# CHIP_ziffy_v4.net
KiCad netlist of a schematic drawn in EAGLE
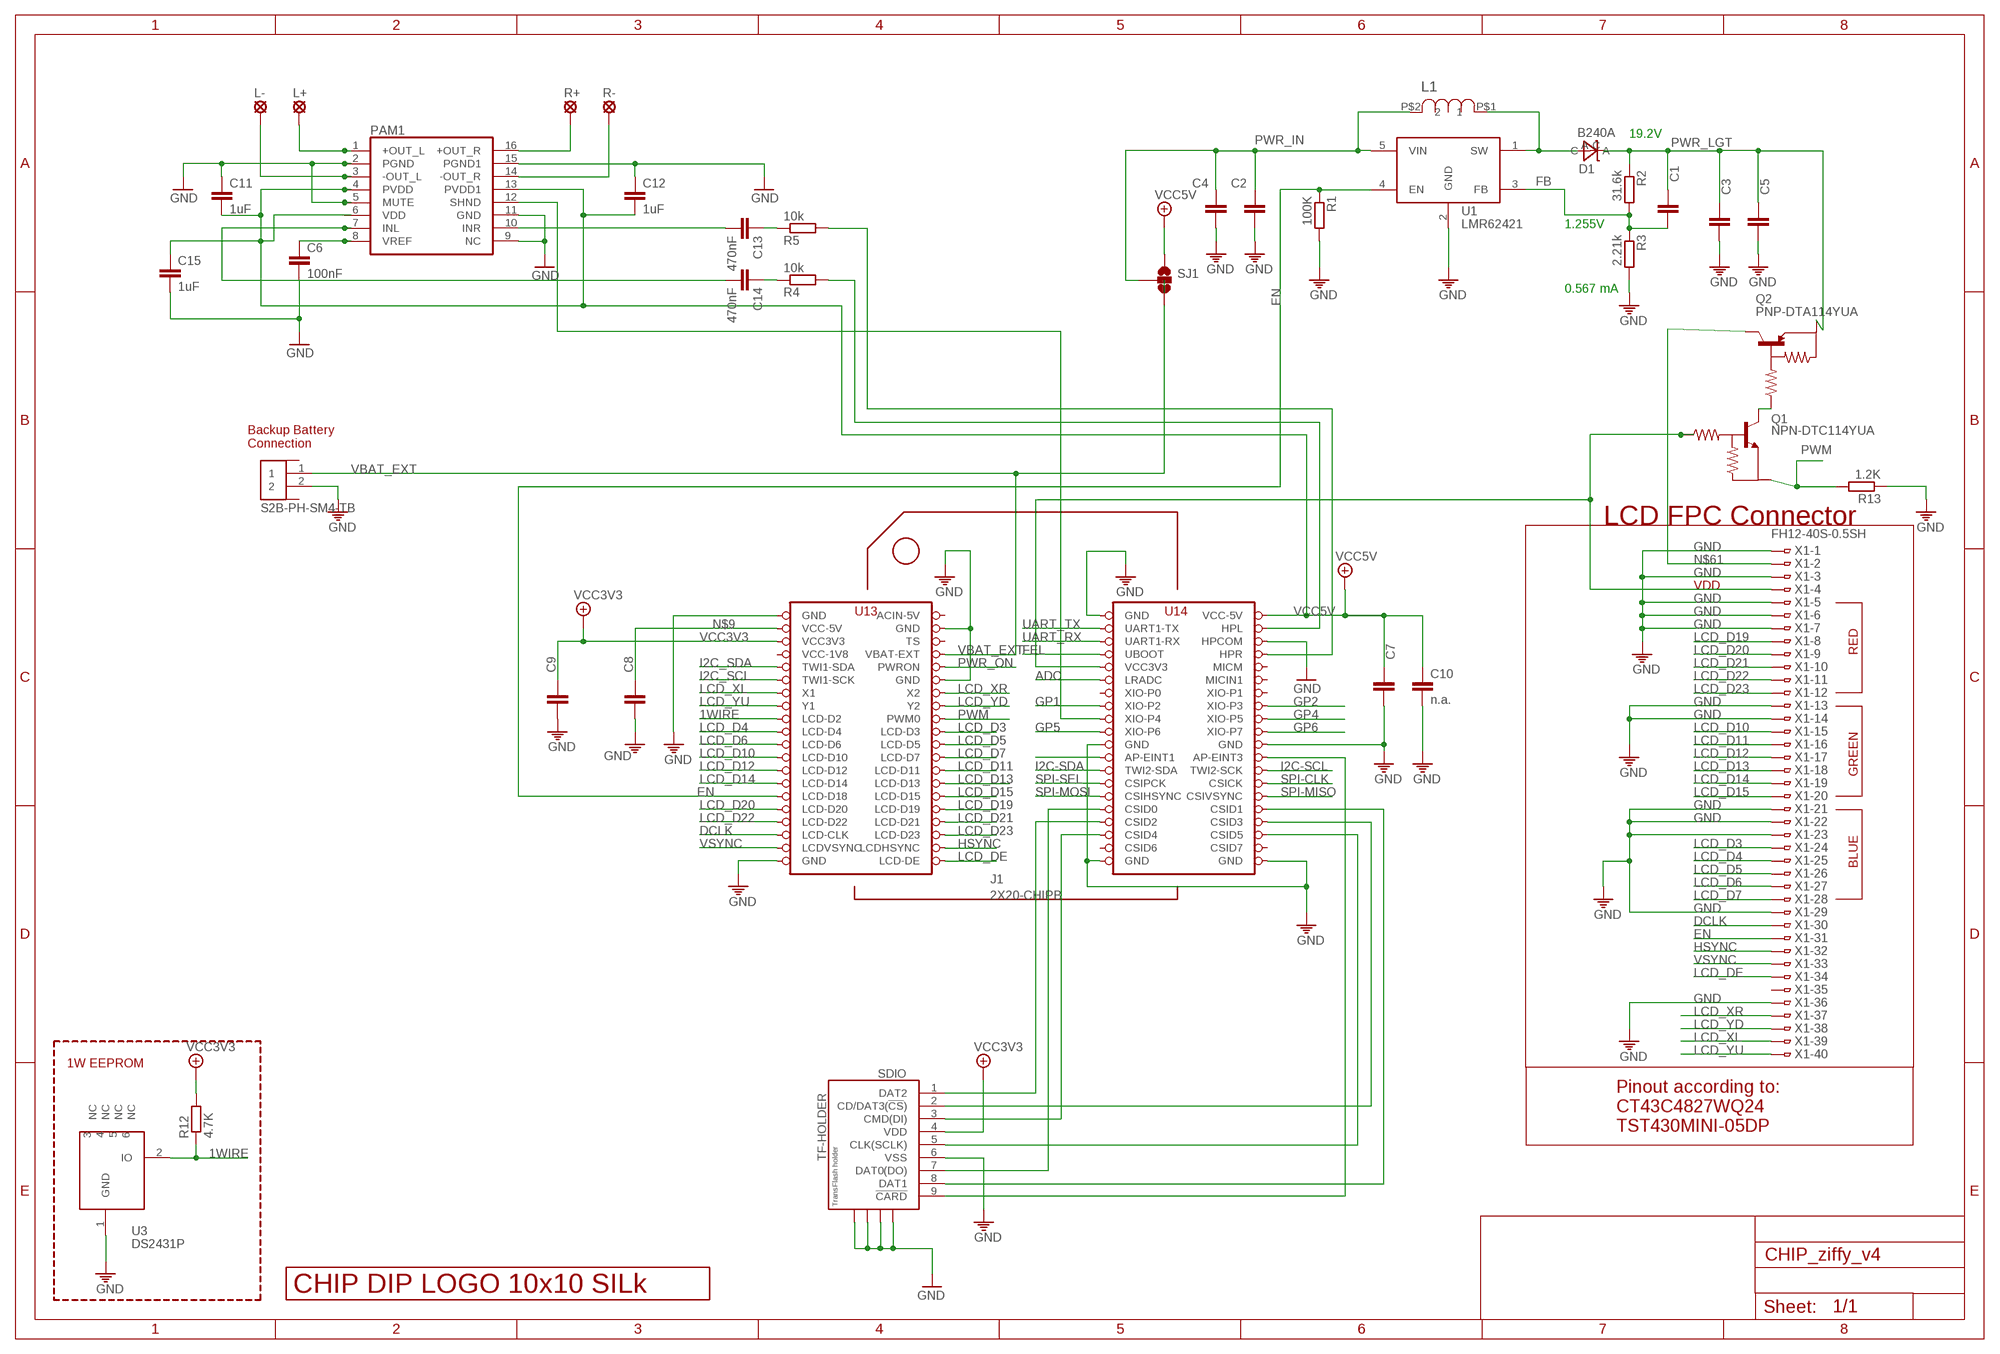
[diagram p0: schematic, sheet 1]

(export (version "E")
  (design (tool "Eeschema 10.0.6"))
  (components
    (comp (ref "C1")
      (value "220pF")
      (footprint "eagle-import:C0805")
      (libsource (lib "eagle-import") (part "C-EUC0805"))
    )
    (comp (ref "C2")
      (value "100nF")
      (footprint "eagle-import:C0805")
      (libsource (lib "eagle-import") (part "C-EUC0805"))
    )
    (comp (ref "C3")
      (value "100nF")
      (footprint "eagle-import:C0805")
      (libsource (lib "eagle-import") (part "C-EUC0805"))
    )
    (comp (ref "C4")
      (value "22uF")
      (footprint "eagle-import:C0805")
      (libsource (lib "eagle-import") (part "C-EUC0805"))
    )
    (comp (ref "C5")
      (value "22uF")
      (footprint "eagle-import:C0805")
      (libsource (lib "eagle-import") (part "C-EUC0805"))
    )
    (comp (ref "C6")
      (value "100nF")
      (footprint "eagle-import:C0805")
      (libsource (lib "eagle-import") (part "C-EUC0805"))
    )
    (comp (ref "C7")
      (value "n.a.")
      (footprint "eagle-import:C0805")
      (libsource (lib "eagle-import") (part "C-EUC0805"))
    )
    (comp (ref "C8")
      (value "100nF")
      (footprint "eagle-import:C0805")
      (libsource (lib "eagle-import") (part "C-EUC0805"))
    )
    (comp (ref "C9")
      (value "100nF")
      (footprint "eagle-import:C0805")
      (libsource (lib "eagle-import") (part "C-EUC0805"))
    )
    (comp (ref "C10")
      (value "n.a.")
      (footprint "eagle-import:C0805")
      (libsource (lib "eagle-import") (part "C-EUC0805"))
    )
    (comp (ref "C11")
      (value "1uF")
      (footprint "eagle-import:C0805")
      (libsource (lib "eagle-import") (part "C-EUC0805"))
    )
    (comp (ref "C12")
      (value "1uF")
      (footprint "eagle-import:C0805")
      (libsource (lib "eagle-import") (part "C-EUC0805"))
    )
    (comp (ref "C13")
      (value "470nF")
      (footprint "eagle-import:C0805")
      (libsource (lib "eagle-import") (part "C-EUC0805"))
    )
    (comp (ref "C14")
      (value "470nF")
      (footprint "eagle-import:C0805")
      (libsource (lib "eagle-import") (part "C-EUC0805"))
    )
    (comp (ref "C15")
      (value "1uF")
      (footprint "eagle-import:C0805")
      (libsource (lib "eagle-import") (part "C-EUC0805"))
    )
    (comp (ref "D1")
      (value "B240A")
      (footprint "eagle-import:DO-214AC")
      (fields (field (name "MFG") "DIGIKEY") (field (name "VENDOR_PART_NUMBER") "B240A-13-F"))
      (libsource (lib "eagle-import") (part "DIODE_SCHTKY_B240"))
    )
    (comp (ref "J1")
      (value "2X20-CHIPB")
      (footprint "eagle-import:2X20CHIP_SM")
      (libsource (lib "eagle-import") (part "2X20-CHIPB"))
    )
    (comp (ref "J3")
      (value "S2B-PH-SM4-TB")
      (footprint "eagle-import:S2B-PH-SM4-TB")
      (fields (field (name "MFG") "DIGIKEY") (field (name "VENDOR_PART_NUMBER") "S2B-PH-SM4-TB(LF)(SN)"))
      (libsource (lib "eagle-import") (part "S2B-PH-SM4-TB"))
    )
    (comp (ref "L+")
      (value "SE11")
      (footprint "eagle-import:SE11")
      (libsource (lib "eagle-import") (part "SE11"))
    )
    (comp (ref "L-")
      (value "SE11")
      (footprint "eagle-import:SE11")
      (libsource (lib "eagle-import") (part "SE11"))
    )
    (comp (ref "L1")
      (value "SRN6045-100M")
      (footprint "eagle-import:SRN6045")
      (fields (field (name "MFG") "DIGIKEY"))
      (libsource (lib "eagle-import") (part "SRN6045-100M"))
    )
    (comp (ref "PAM1")
      (value "PAM8403")
      (footprint "eagle-import:SOP-16")
      (libsource (lib "eagle-import") (part "PAM8403"))
    )
    (comp (ref "Q1")
      (value "NPN-DTC114YUA")
      (footprint "eagle-import:SOT323")
      (libsource (lib "eagle-import") (part "NPN-DTC114YUA"))
    )
    (comp (ref "Q2")
      (value "PNP-DTA114YUA")
      (footprint "eagle-import:SOT323")
      (libsource (lib "eagle-import") (part "PNP-DTA114YUA"))
    )
    (comp (ref "R+")
      (value "SE11")
      (footprint "eagle-import:SE11")
      (libsource (lib "eagle-import") (part "SE11"))
    )
    (comp (ref "R-")
      (value "SE11")
      (footprint "eagle-import:SE11")
      (libsource (lib "eagle-import") (part "SE11"))
    )
    (comp (ref "R1")
      (value "100K")
      (footprint "eagle-import:M0805")
      (libsource (lib "eagle-import") (part "R-EU_M0805"))
    )
    (comp (ref "R2")
      (value "31.6k")
      (footprint "eagle-import:M0805")
      (libsource (lib "eagle-import") (part "R-EU_M0805"))
    )
    (comp (ref "R3")
      (value "2.21k")
      (footprint "eagle-import:M0805")
      (libsource (lib "eagle-import") (part "R-EU_M0805"))
    )
    (comp (ref "R4")
      (value "10k")
      (footprint "eagle-import:R0805")
      (libsource (lib "eagle-import") (part "R-EU_R0805"))
    )
    (comp (ref "R5")
      (value "10k")
      (footprint "eagle-import:R0805")
      (libsource (lib "eagle-import") (part "R-EU_R0805"))
    )
    (comp (ref "R12")
      (value "4.7K")
      (footprint "eagle-import:M0805")
      (libsource (lib "eagle-import") (part "R-EU_M0805"))
    )
    (comp (ref "R13")
      (value "1.2K")
      (footprint "eagle-import:M0805")
      (libsource (lib "eagle-import") (part "R-EU_M0805"))
    )
    (comp (ref "SDIO")
      (value "TF-HOLDER")
      (footprint "eagle-import:TF-PULL")
      (libsource (lib "eagle-import") (part "TF-HOLDER"))
    )
    (comp (ref "SJ1")
      (value "SOLDERJUMPER_2WAYT")
      (footprint "eagle-import:SJ_2")
      (libsource (lib "eagle-import") (part "SOLDERJUMPER_2WAYT"))
    )
    (comp (ref "U$2")
      (value "LOGO_10X10_SILK")
      (footprint "eagle-import:LOGO2_10X10_SILK")
      (libsource (lib "eagle-import") (part "LOGO_10X10_SILK"))
    )
    (comp (ref "U1")
      (value "LMR62421")
      (footprint "eagle-import:SOT23-5")
      (fields (field (name "MFG") "DIGIKEY") (field (name "VENDOR_PART_NUMBER") "LMR62421XMFE/NOPB"))
      (libsource (lib "eagle-import") (part "LMR62421"))
    )
    (comp (ref "U3")
      (value "DS2431P")
      (footprint "eagle-import:TSOC6")
      (fields (field (name "MFG") "DIGIKEY") (field (name "VENDOR_PART_NUMBER") "DS2431P+T&R"))
      (libsource (lib "eagle-import") (part "DS2431P"))
    )
    (comp (ref "X1")
      (value "FH12-40S-0.5SH")
      (footprint "eagle-import:FH12-40S-0.5SH")
      (fields (field (name "MFG") "DIGIKEY") (field (name "VENDOR_PART_NUMBER") "FH12-40S-0.5SH(55)"))
      (libsource (lib "eagle-import") (part "FH12-40S-0.5SH"))
    )
  )
  (nets
    (net (code "1") (name "/1WIRE") (class "Default")
      (node (ref "J1") (pin "LCD-D2") (pinfunction "LCD-D2_LCD-D2") (pintype "passive"))
      (node (ref "R12") (pin "1") (pinfunction "1_1") (pintype "passive"))
      (node (ref "U3") (pin "2") (pinfunction "IO_2") (pintype "bidirectional"))
    )
    (net (code "2") (name "/ADC") (class "Default")
      (node (ref "J1") (pin "LRADC") (pinfunction "LRADC_LRADC") (pintype "passive"))
    )
    (net (code "3") (name "/DCLK") (class "Default")
      (node (ref "J1") (pin "LCD-CLK") (pinfunction "LCD-CLK_LCD-CLK") (pintype "passive"))
      (node (ref "X1") (pin "30") (pinfunction "1_30") (pintype "passive"))
    )
    (net (code "4") (name "/EN") (class "Default")
      (node (ref "J1") (pin "LCD-D18") (pinfunction "LCD-D18_LCD-D18") (pintype "passive"))
      (node (ref "R1") (pin "1") (pinfunction "1_1") (pintype "passive"))
      (node (ref "U1") (pin "4") (pinfunction "EN_4") (pintype "bidirectional"))
      (node (ref "X1") (pin "31") (pinfunction "1_31") (pintype "passive"))
    )
    (net (code "5") (name "/FB") (class "Default")
      (node (ref "C1") (pin "2") (pinfunction "2_2") (pintype "passive"))
      (node (ref "R2") (pin "2") (pinfunction "2_2") (pintype "passive"))
      (node (ref "R3") (pin "1") (pinfunction "1_1") (pintype "passive"))
      (node (ref "U1") (pin "3") (pinfunction "FB_3") (pintype "bidirectional"))
    )
    (net (code "6") (name "/FEL") (class "Default")
      (node (ref "J1") (pin "FEL") (pinfunction "UBOOT_FEL") (pintype "passive"))
    )
    (net (code "7") (name "/GP1") (class "Default")
      (node (ref "J1") (pin "XIO-P2") (pinfunction "XIO-P2_XIO-P2") (pintype "passive"))
    )
    (net (code "8") (name "/GP2") (class "Default")
      (node (ref "J1") (pin "XIO-P3") (pinfunction "XIO-P3_XIO-P3") (pintype "passive"))
    )
    (net (code "9") (name "/GP4") (class "Default")
      (node (ref "J1") (pin "XIO-P5") (pinfunction "XIO-P5_XIO-P5") (pintype "passive"))
    )
    (net (code "10") (name "/GP5") (class "Default")
      (node (ref "J1") (pin "XIO-P6") (pinfunction "XIO-P6_XIO-P6") (pintype "passive"))
    )
    (net (code "11") (name "/GP6") (class "Default")
      (node (ref "J1") (pin "XIO-P7") (pinfunction "XIO-P7_XIO-P7") (pintype "passive"))
    )
    (net (code "12") (name "/HSYNC") (class "Default")
      (node (ref "J1") (pin "LCD-HSYNC") (pinfunction "LCDHSYNC_LCD-HSYNC") (pintype "passive"))
      (node (ref "X1") (pin "32") (pinfunction "1_32") (pintype "passive"))
    )
    (net (code "13") (name "/I2C-SCL") (class "Default")
      (node (ref "J1") (pin "TWI2-SCK") (pinfunction "TWI2-SCK_TWI2-SCK") (pintype "passive"))
    )
    (net (code "14") (name "/I2C-SDA") (class "Default")
      (node (ref "J1") (pin "TWI2-SDA") (pinfunction "TWI2-SDA_TWI2-SDA") (pintype "passive"))
    )
    (net (code "15") (name "/I2C_SCL") (class "Default")
      (node (ref "J1") (pin "TWI1-SCK") (pinfunction "TWI1-SCK_TWI1-SCK") (pintype "passive"))
    )
    (net (code "16") (name "/I2C_SDA") (class "Default")
      (node (ref "J1") (pin "TWI1-SDA") (pinfunction "TWI1-SDA_TWI1-SDA") (pintype "passive"))
    )
    (net (code "17") (name "/LCD_D3") (class "Default")
      (node (ref "J1") (pin "LCD-D3") (pinfunction "LCD-D3_LCD-D3") (pintype "passive"))
      (node (ref "X1") (pin "24") (pinfunction "1_24") (pintype "passive"))
    )
    (net (code "18") (name "/LCD_D4") (class "Default")
      (node (ref "J1") (pin "LCD-D4") (pinfunction "LCD-D4_LCD-D4") (pintype "passive"))
      (node (ref "X1") (pin "25") (pinfunction "1_25") (pintype "passive"))
    )
    (net (code "19") (name "/LCD_D5") (class "Default")
      (node (ref "J1") (pin "LCD-D5") (pinfunction "LCD-D5_LCD-D5") (pintype "passive"))
      (node (ref "X1") (pin "26") (pinfunction "1_26") (pintype "passive"))
    )
    (net (code "20") (name "/LCD_D6") (class "Default")
      (node (ref "J1") (pin "LCD-D6") (pinfunction "LCD-D6_LCD-D6") (pintype "passive"))
      (node (ref "X1") (pin "27") (pinfunction "1_27") (pintype "passive"))
    )
    (net (code "21") (name "/LCD_D7") (class "Default")
      (node (ref "J1") (pin "LCD-D7") (pinfunction "LCD-D7_LCD-D7") (pintype "passive"))
      (node (ref "X1") (pin "28") (pinfunction "1_28") (pintype "passive"))
    )
    (net (code "22") (name "/LCD_D10") (class "Default")
      (node (ref "J1") (pin "LCD-D10") (pinfunction "LCD-D10_LCD-D10") (pintype "passive"))
      (node (ref "X1") (pin "15") (pinfunction "1_15") (pintype "passive"))
    )
    (net (code "23") (name "/LCD_D11") (class "Default")
      (node (ref "J1") (pin "LCD-D11") (pinfunction "LCD-D11_LCD-D11") (pintype "passive"))
      (node (ref "X1") (pin "16") (pinfunction "1_16") (pintype "passive"))
    )
    (net (code "24") (name "/LCD_D12") (class "Default")
      (node (ref "J1") (pin "LCD-D12") (pinfunction "LCD-D12_LCD-D12") (pintype "passive"))
      (node (ref "X1") (pin "17") (pinfunction "1_17") (pintype "passive"))
    )
    (net (code "25") (name "/LCD_D13") (class "Default")
      (node (ref "J1") (pin "LCD-D13") (pinfunction "LCD-D13_LCD-D13") (pintype "passive"))
      (node (ref "X1") (pin "18") (pinfunction "1_18") (pintype "passive"))
    )
    (net (code "26") (name "/LCD_D14") (class "Default")
      (node (ref "J1") (pin "LCD-D14") (pinfunction "LCD-D14_LCD-D14") (pintype "passive"))
      (node (ref "X1") (pin "19") (pinfunction "1_19") (pintype "passive"))
    )
    (net (code "27") (name "/LCD_D15") (class "Default")
      (node (ref "J1") (pin "LCD-D15") (pinfunction "LCD-D15_LCD-D15") (pintype "passive"))
      (node (ref "X1") (pin "20") (pinfunction "1_20") (pintype "passive"))
    )
    (net (code "28") (name "/LCD_D19") (class "Default")
      (node (ref "J1") (pin "LCD-D19") (pinfunction "LCD-D19_LCD-D19") (pintype "passive"))
      (node (ref "X1") (pin "8") (pinfunction "1_8") (pintype "passive"))
    )
    (net (code "29") (name "/LCD_D20") (class "Default")
      (node (ref "J1") (pin "LCD-D20") (pinfunction "LCD-D20_LCD-D20") (pintype "passive"))
      (node (ref "X1") (pin "9") (pinfunction "1_9") (pintype "passive"))
    )
    (net (code "30") (name "/LCD_D21") (class "Default")
      (node (ref "J1") (pin "LCD-D21") (pinfunction "LCD-D21_LCD-D21") (pintype "passive"))
      (node (ref "X1") (pin "10") (pinfunction "1_10") (pintype "passive"))
    )
    (net (code "31") (name "/LCD_D22") (class "Default")
      (node (ref "J1") (pin "LCD-D22") (pinfunction "LCD-D22_LCD-D22") (pintype "passive"))
      (node (ref "X1") (pin "11") (pinfunction "1_11") (pintype "passive"))
    )
    (net (code "32") (name "/LCD_D23") (class "Default")
      (node (ref "J1") (pin "LCD-D23") (pinfunction "LCD-D23_LCD-D23") (pintype "passive"))
      (node (ref "X1") (pin "12") (pinfunction "1_12") (pintype "passive"))
    )
    (net (code "33") (name "/LCD_DE") (class "Default")
      (node (ref "J1") (pin "LCD-DE") (pinfunction "LCD-DE_LCD-DE") (pintype "passive"))
      (node (ref "X1") (pin "34") (pinfunction "1_34") (pintype "passive"))
    )
    (net (code "34") (name "/LCD_XL") (class "Default")
      (node (ref "J1") (pin "X1") (pinfunction "X1_X1") (pintype "passive"))
      (node (ref "X1") (pin "39") (pinfunction "1_39") (pintype "passive"))
    )
    (net (code "35") (name "/LCD_XR") (class "Default")
      (node (ref "J1") (pin "X2") (pinfunction "X2_X2") (pintype "passive"))
      (node (ref "X1") (pin "37") (pinfunction "1_37") (pintype "passive"))
    )
    (net (code "36") (name "/LCD_YD") (class "Default")
      (node (ref "J1") (pin "Y2") (pinfunction "Y2_Y2") (pintype "passive"))
      (node (ref "X1") (pin "38") (pinfunction "1_38") (pintype "passive"))
    )
    (net (code "37") (name "/LCD_YU") (class "Default")
      (node (ref "J1") (pin "Y1") (pinfunction "Y1_Y1") (pintype "passive"))
      (node (ref "X1") (pin "40") (pinfunction "1_40") (pintype "passive"))
    )
    (net (code "38") (name "/N$9") (class "Default")
      (node (ref "C8") (pin "1") (pinfunction "1_1") (pintype "passive"))
      (node (ref "J1") (pin "VCC5V@0") (pinfunction "VCC-5V_VCC5V@0") (pintype "power_in"))
    )
    (net (code "39") (name "/N$61") (class "Default")
      (node (ref "Q2") (pin "3") (pinfunction "OUT_3") (pintype "passive"))
      (node (ref "X1") (pin "2") (pinfunction "1_2") (pintype "passive"))
    )
    (net (code "40") (name "/PWM") (class "Default")
      (node (ref "J1") (pin "PWM0") (pinfunction "PWM0_PWM0") (pintype "passive"))
      (node (ref "Q1") (pin "2") (pinfunction "GND_2") (pintype "passive"))
      (node (ref "R13") (pin "2") (pinfunction "2_2") (pintype "passive"))
    )
    (net (code "41") (name "/PWR_IN") (class "Default")
      (node (ref "C2") (pin "1") (pinfunction "1_1") (pintype "passive"))
      (node (ref "C4") (pin "1") (pinfunction "1_1") (pintype "passive"))
      (node (ref "L1") (pin "P$2") (pinfunction "2_P$2") (pintype "passive"))
      (node (ref "SJ1") (pin "2") (pinfunction "2_2") (pintype "passive"))
      (node (ref "U1") (pin "5") (pinfunction "VIN_5") (pintype "bidirectional"))
    )
    (net (code "42") (name "/PWR_LGT") (class "Default")
      (node (ref "C1") (pin "1") (pinfunction "1_1") (pintype "passive"))
      (node (ref "C3") (pin "1") (pinfunction "1_1") (pintype "passive"))
      (node (ref "C5") (pin "1") (pinfunction "1_1") (pintype "passive"))
      (node (ref "D1") (pin "C") (pinfunction "C_C") (pintype "bidirectional"))
      (node (ref "Q2") (pin "2") (pinfunction "GND_2") (pintype "passive"))
      (node (ref "R2") (pin "1") (pinfunction "1_1") (pintype "passive"))
    )
    (net (code "43") (name "/PWR_ON") (class "Default")
      (node (ref "J1") (pin "PWRON") (pinfunction "PWRON_PWRON") (pintype "passive"))
    )
    (net (code "44") (name "/SPI-CLK") (class "Default")
      (node (ref "J1") (pin "CSICK") (pinfunction "CSICK_CSICK") (pintype "passive"))
    )
    (net (code "45") (name "/SPI-MISO") (class "Default")
      (node (ref "J1") (pin "CSIVSYNC") (pinfunction "CSIVSYNC_CSIVSYNC") (pintype "passive"))
    )
    (net (code "46") (name "/SPI-MOSI") (class "Default")
      (node (ref "J1") (pin "CSIHSYNC") (pinfunction "CSIHSYNC_CSIHSYNC") (pintype "passive"))
    )
    (net (code "47") (name "/SPI-SEL") (class "Default")
      (node (ref "J1") (pin "CSIPCK") (pinfunction "CSIPCK_CSIPCK") (pintype "passive"))
    )
    (net (code "48") (name "/UART_RX") (class "Default")
      (node (ref "J1") (pin "UART1-RX") (pinfunction "UART1-RX_UART1-RX") (pintype "passive"))
    )
    (net (code "49") (name "/UART_TX") (class "Default")
      (node (ref "J1") (pin "UART1-TX") (pinfunction "UART1-TX_UART1-TX") (pintype "passive"))
    )
    (net (code "50") (name "/VBAT_EXT") (class "Default")
      (node (ref "J1") (pin "BAT") (pinfunction "VBAT-EXT_BAT") (pintype "passive"))
      (node (ref "J3") (pin "1") (pinfunction "1_1") (pintype "bidirectional"))
      (node (ref "SJ1") (pin "3") (pinfunction "3_3") (pintype "passive"))
    )
    (net (code "51") (name "/VCC-1V8") (class "Default")
      (node (ref "J1") (pin "VCC1V8") (pinfunction "VCC-1V8_VCC1V8") (pintype "power_in"))
    )
    (net (code "52") (name "/VSYNC") (class "Default")
      (node (ref "J1") (pin "LCD-VSYNC") (pinfunction "LCDVSYNC_LCD-VSYNC") (pintype "passive"))
      (node (ref "X1") (pin "33") (pinfunction "1_33") (pintype "passive"))
    )
    (net (code "53") (name "GND") (class "Default")
      (node (ref "C10") (pin "2") (pinfunction "2_2") (pintype "passive"))
      (node (ref "C11") (pin "1") (pinfunction "1_1") (pintype "passive"))
      (node (ref "C12") (pin "1") (pinfunction "1_1") (pintype "passive"))
      (node (ref "C15") (pin "2") (pinfunction "2_2") (pintype "passive"))
      (node (ref "C2") (pin "2") (pinfunction "2_2") (pintype "passive"))
      (node (ref "C3") (pin "2") (pinfunction "2_2") (pintype "passive"))
      (node (ref "C4") (pin "2") (pinfunction "2_2") (pintype "passive"))
      (node (ref "C5") (pin "2") (pinfunction "2_2") (pintype "passive"))
      (node (ref "C6") (pin "2") (pinfunction "2_2") (pintype "passive"))
      (node (ref "C7") (pin "2") (pinfunction "2_2") (pintype "passive"))
      (node (ref "C8") (pin "2") (pinfunction "2_2") (pintype "passive"))
      (node (ref "C9") (pin "2") (pinfunction "2_2") (pintype "passive"))
      (node (ref "J1") (pin "GND@1") (pinfunction "GND_GND@1") (pintype "power_in"))
      (node (ref "J1") (pin "GND@10") (pinfunction "GND_GND@10") (pintype "power_in"))
      (node (ref "J1") (pin "GND@2") (pinfunction "GND_GND@2") (pintype "power_in"))
      (node (ref "J1") (pin "GND@3") (pinfunction "GND_GND@3") (pintype "power_in"))
      (node (ref "J1") (pin "GND@4") (pinfunction "GND_GND@4") (pintype "power_in"))
      (node (ref "J1") (pin "GND@5") (pinfunction "GND_GND@5") (pintype "power_in"))
      (node (ref "J1") (pin "GND@6") (pinfunction "GND_GND@6") (pintype "power_in"))
      (node (ref "J1") (pin "GND@7") (pinfunction "GND_GND@7") (pintype "power_in"))
      (node (ref "J1") (pin "GND@8") (pinfunction "GND_GND@8") (pintype "power_in"))
      (node (ref "J1") (pin "HPCOM") (pinfunction "HPCOM_HPCOM") (pintype "passive"))
      (node (ref "J3") (pin "2") (pinfunction "2_2") (pintype "bidirectional"))
      (node (ref "PAM1") (pin "11") (pinfunction "GND_11") (pintype "output"))
      (node (ref "PAM1") (pin "15") (pinfunction "PGND1_15") (pintype "output"))
      (node (ref "PAM1") (pin "2") (pinfunction "PGND_2") (pintype "input"))
      (node (ref "PAM1") (pin "5") (pinfunction "MUTE_5") (pintype "input"))
      (node (ref "PAM1") (pin "9") (pinfunction "NC_9") (pintype "output"))
      (node (ref "R1") (pin "2") (pinfunction "2_2") (pintype "passive"))
      (node (ref "R13") (pin "1") (pinfunction "1_1") (pintype "passive"))
      (node (ref "R3") (pin "2") (pinfunction "2_2") (pintype "passive"))
      (node (ref "SDIO") (pin "6") (pinfunction "VSS_6") (pintype "power_in"))
      (node (ref "SDIO") (pin "S1") (pinfunction "S1_S1") (pintype "passive"))
      (node (ref "SDIO") (pin "S2") (pinfunction "S2_S2") (pintype "passive"))
      (node (ref "SDIO") (pin "S3") (pinfunction "S3_S3") (pintype "passive"))
      (node (ref "SDIO") (pin "S4") (pinfunction "S4_S4") (pintype "passive"))
      (node (ref "U1") (pin "2") (pinfunction "GND_2") (pintype "bidirectional"))
      (node (ref "U3") (pin "1") (pinfunction "GND_1") (pintype "bidirectional"))
      (node (ref "X1") (pin "1") (pinfunction "1_1") (pintype "passive"))
      (node (ref "X1") (pin "13") (pinfunction "1_13") (pintype "passive"))
      (node (ref "X1") (pin "14") (pinfunction "1_14") (pintype "passive"))
      (node (ref "X1") (pin "21") (pinfunction "1_21") (pintype "passive"))
      (node (ref "X1") (pin "22") (pinfunction "1_22") (pintype "passive"))
      (node (ref "X1") (pin "23") (pinfunction "1_23") (pintype "passive"))
      (node (ref "X1") (pin "29") (pinfunction "1_29") (pintype "passive"))
      (node (ref "X1") (pin "3") (pinfunction "1_3") (pintype "passive"))
      (node (ref "X1") (pin "36") (pinfunction "1_36") (pintype "passive"))
      (node (ref "X1") (pin "5") (pinfunction "1_5") (pintype "passive"))
      (node (ref "X1") (pin "6") (pinfunction "1_6") (pintype "passive"))
      (node (ref "X1") (pin "7") (pinfunction "1_7") (pintype "passive"))
    )
    (net (code "54") (name "Net-(C13-Pad1)") (class "Default")
      (node (ref "C13") (pin "1") (pinfunction "1_1") (pintype "passive"))
      (node (ref "R5") (pin "1") (pinfunction "1_1") (pintype "passive"))
    )
    (net (code "55") (name "Net-(C14-Pad1)") (class "Default")
      (node (ref "C14") (pin "1") (pinfunction "1_1") (pintype "passive"))
      (node (ref "R4") (pin "1") (pinfunction "1_1") (pintype "passive"))
    )
    (net (code "56") (name "Net-(J1-PadHPL)") (class "Default")
      (node (ref "J1") (pin "HPL") (pinfunction "HPL_HPL") (pintype "passive"))
      (node (ref "R4") (pin "2") (pinfunction "2_2") (pintype "passive"))
    )
    (net (code "57") (name "Net-(J1-PadHPR)") (class "Default")
      (node (ref "J1") (pin "HPR") (pinfunction "HPR_HPR") (pintype "passive"))
      (node (ref "R5") (pin "2") (pinfunction "2_2") (pintype "passive"))
    )
    (net (code "58") (name "Net-(L1-1)") (class "Default")
      (node (ref "D1") (pin "A") (pinfunction "A_A") (pintype "bidirectional"))
      (node (ref "L1") (pin "P$1") (pinfunction "1_P$1") (pintype "passive"))
      (node (ref "U1") (pin "1") (pinfunction "SW_1") (pintype "bidirectional"))
    )
    (net (code "59") (name "Net-(PAM1-+OUT_L)") (class "Default")
      (node (ref "L+") (pin "MP") (pinfunction "MP_MP") (pintype "passive"))
      (node (ref "PAM1") (pin "1") (pinfunction "+OUT_L_1") (pintype "input"))
    )
    (net (code "60") (name "Net-(PAM1-+OUT_R)") (class "Default")
      (node (ref "PAM1") (pin "16") (pinfunction "+OUT_R_16") (pintype "output"))
      (node (ref "R+") (pin "MP") (pinfunction "MP_MP") (pintype "passive"))
    )
    (net (code "61") (name "Net-(PAM1--OUT_L)") (class "Default")
      (node (ref "L-") (pin "MP") (pinfunction "MP_MP") (pintype "passive"))
      (node (ref "PAM1") (pin "3") (pinfunction "-OUT_L_3") (pintype "input"))
    )
    (net (code "62") (name "Net-(PAM1--OUT_R)") (class "Default")
      (node (ref "PAM1") (pin "14") (pinfunction "-OUT_R_14") (pintype "output"))
      (node (ref "R-") (pin "MP") (pinfunction "MP_MP") (pintype "passive"))
    )
    (net (code "63") (name "Net-(PAM1-INL)") (class "Default")
      (node (ref "C14") (pin "2") (pinfunction "2_2") (pintype "passive"))
      (node (ref "PAM1") (pin "7") (pinfunction "INL_7") (pintype "input"))
    )
    (net (code "64") (name "Net-(PAM1-INR)") (class "Default")
      (node (ref "C13") (pin "2") (pinfunction "2_2") (pintype "passive"))
      (node (ref "PAM1") (pin "10") (pinfunction "INR_10") (pintype "output"))
    )
    (net (code "65") (name "Net-(PAM1-SHND)") (class "Default")
      (node (ref "J1") (pin "XIO-P4") (pinfunction "XIO-P4_XIO-P4") (pintype "passive"))
      (node (ref "PAM1") (pin "12") (pinfunction "SHND_12") (pintype "output"))
    )
    (net (code "66") (name "Net-(PAM1-VREF)") (class "Default")
      (node (ref "C6") (pin "1") (pinfunction "1_1") (pintype "passive"))
      (node (ref "PAM1") (pin "8") (pinfunction "VREF_8") (pintype "input"))
    )
    (net (code "67") (name "Net-(Q1-IN)") (class "Default")
      (node (ref "J1") (pin "VCC3V3@1") (pinfunction "VCC3V3_VCC3V3@1") (pintype "power_in"))
      (node (ref "Q1") (pin "1") (pinfunction "IN_1") (pintype "passive"))
      (node (ref "X1") (pin "4") (pinfunction "1_4") (pintype "passive"))
    )
    (net (code "68") (name "Net-(Q1-OUT)") (class "Default")
      (node (ref "Q1") (pin "3") (pinfunction "OUT_3") (pintype "passive"))
      (node (ref "Q2") (pin "1") (pinfunction "IN_1") (pintype "passive"))
    )
    (net (code "69") (name "Net-(SDIO-CD{slash}DAT3(~{CS}))") (class "Default")
      (node (ref "J1") (pin "CSID3") (pinfunction "CSID3_CSID3") (pintype "passive"))
      (node (ref "SDIO") (pin "2") (pinfunction "CD/DAT3(~{CS})_2") (pintype "bidirectional"))
    )
    (net (code "70") (name "Net-(SDIO-CLK(SCLK))") (class "Default")
      (node (ref "J1") (pin "CSID5") (pinfunction "CSID5_CSID5") (pintype "passive"))
      (node (ref "SDIO") (pin "5") (pinfunction "CLK(SCLK)_5") (pintype "input"))
    )
    (net (code "71") (name "Net-(SDIO-CMD(DI))") (class "Default")
      (node (ref "J1") (pin "CSID4") (pinfunction "CSID4_CSID4") (pintype "passive"))
      (node (ref "SDIO") (pin "3") (pinfunction "CMD(DI)_3") (pintype "bidirectional"))
    )
    (net (code "72") (name "Net-(SDIO-DAT0(DO))") (class "Default")
      (node (ref "J1") (pin "CSID0") (pinfunction "CSID0_CSID0") (pintype "passive"))
      (node (ref "SDIO") (pin "7") (pinfunction "DAT0(DO)_7") (pintype "bidirectional"))
    )
    (net (code "73") (name "Net-(SDIO-DAT1)") (class "Default")
      (node (ref "J1") (pin "CSID1") (pinfunction "CSID1_CSID1") (pintype "passive"))
      (node (ref "SDIO") (pin "8") (pinfunction "DAT1_8") (pintype "bidirectional"))
    )
    (net (code "74") (name "Net-(SDIO-DAT2)") (class "Default")
      (node (ref "J1") (pin "CSID2") (pinfunction "CSID2_CSID2") (pintype "passive"))
      (node (ref "SDIO") (pin "1") (pinfunction "DAT2_1") (pintype "bidirectional"))
    )
    (net (code "75") (name "Net-(SDIO-~{CARD})") (class "Default")
      (node (ref "J1") (pin "AP-EINT3") (pinfunction "AP-EINT3_AP-EINT3") (pintype "passive"))
      (node (ref "SDIO") (pin "9") (pinfunction "~{CARD}_9") (pintype "passive"))
    )
    (net (code "76") (name "VCC3V3") (class "Default")
      (node (ref "C9") (pin "1") (pinfunction "1_1") (pintype "passive"))
      (node (ref "J1") (pin "VCC3V3") (pinfunction "VCC3V3_VCC3V3") (pintype "power_in"))
      (node (ref "R12") (pin "2") (pinfunction "2_2") (pintype "passive"))
      (node (ref "SDIO") (pin "4") (pinfunction "VDD_4") (pintype "power_in"))
    )
    (net (code "77") (name "VCC5V") (class "Default")
      (node (ref "C10") (pin "1") (pinfunction "1_1") (pintype "passive"))
      (node (ref "C11") (pin "2") (pinfunction "2_2") (pintype "passive"))
      (node (ref "C12") (pin "2") (pinfunction "2_2") (pintype "passive"))
      (node (ref "C15") (pin "1") (pinfunction "1_1") (pintype "passive"))
      (node (ref "C7") (pin "1") (pinfunction "1_1") (pintype "passive"))
      (node (ref "J1") (pin "VCC5V@1") (pinfunction "VCC-5V_VCC5V@1") (pintype "power_in"))
      (node (ref "PAM1") (pin "13") (pinfunction "PVDD1_13") (pintype "output"))
      (node (ref "PAM1") (pin "4") (pinfunction "PVDD_4") (pintype "input"))
      (node (ref "PAM1") (pin "6") (pinfunction "VDD_6") (pintype "input"))
      (node (ref "SJ1") (pin "1") (pinfunction "1_1") (pintype "passive"))
    )
    (net (code "78") (name "unconnected-(J1-ACIN-5V-PadCHG-IN)") (class "Default")
      (node (ref "J1") (pin "CHG-IN") (pinfunction "ACIN-5V_CHG-IN") (pintype "passive"))
    )
    (net (code "79") (name "unconnected-(J1-PadAP-EINT1)") (class "Default")
      (node (ref "J1") (pin "AP-EINT1") (pinfunction "AP-EINT1_AP-EINT1") (pintype "passive"))
    )
    (net (code "80") (name "unconnected-(J1-PadCSID6)") (class "Default")
      (node (ref "J1") (pin "CSID6") (pinfunction "CSID6_CSID6") (pintype "passive"))
    )
    (net (code "81") (name "unconnected-(J1-PadCSID7)") (class "Default")
      (node (ref "J1") (pin "CSID7") (pinfunction "CSID7_CSID7") (pintype "passive"))
    )
    (net (code "82") (name "unconnected-(J1-PadMICIN1)") (class "Default")
      (node (ref "J1") (pin "MICIN1") (pinfunction "MICIN1_MICIN1") (pintype "passive"))
    )
    (net (code "83") (name "unconnected-(J1-PadMICM)") (class "Default")
      (node (ref "J1") (pin "MICM") (pinfunction "MICM_MICM") (pintype "passive"))
    )
    (net (code "84") (name "unconnected-(J1-PadTS)") (class "Default")
      (node (ref "J1") (pin "TS") (pinfunction "TS_TS") (pintype "passive"))
    )
    (net (code "85") (name "unconnected-(J1-PadXIO-P0)") (class "Default")
      (node (ref "J1") (pin "XIO-P0") (pinfunction "XIO-P0_XIO-P0") (pintype "passive"))
    )
    (net (code "86") (name "unconnected-(J1-PadXIO-P1)") (class "Default")
      (node (ref "J1") (pin "XIO-P1") (pinfunction "XIO-P1_XIO-P1") (pintype "passive"))
    )
    (net (code "87") (name "unconnected-(J3-PadMNT1)") (class "Default")
      (node (ref "J3") (pin "MNT1") (pinfunction "MNT1_MNT1") (pintype "no_connect"))
    )
    (net (code "88") (name "unconnected-(J3-PadMNT2)") (class "Default")
      (node (ref "J3") (pin "MNT2") (pinfunction "MNT2_MNT2") (pintype "no_connect"))
    )
    (net (code "89") (name "unconnected-(U3-NC-Pad3)") (class "Default")
      (node (ref "U3") (pin "3") (pinfunction "NC_3") (pintype "bidirectional"))
    )
    (net (code "90") (name "unconnected-(U3-NC-Pad4)") (class "Default")
      (node (ref "U3") (pin "4") (pinfunction "NC_4") (pintype "bidirectional"))
    )
    (net (code "91") (name "unconnected-(U3-NC-Pad5)") (class "Default")
      (node (ref "U3") (pin "5") (pinfunction "NC_5") (pintype "bidirectional"))
    )
    (net (code "92") (name "unconnected-(U3-NC-Pad6)") (class "Default")
      (node (ref "U3") (pin "6") (pinfunction "NC_6") (pintype "bidirectional"))
    )
    (net (code "93") (name "unconnected-(X1AC-1-Pad35)") (class "Default")
      (node (ref "X1") (pin "35") (pinfunction "1_35") (pintype "passive"))
    )
  )
)
